# 21.net
KiCad netlist of a schematic drawn in Altium Designer
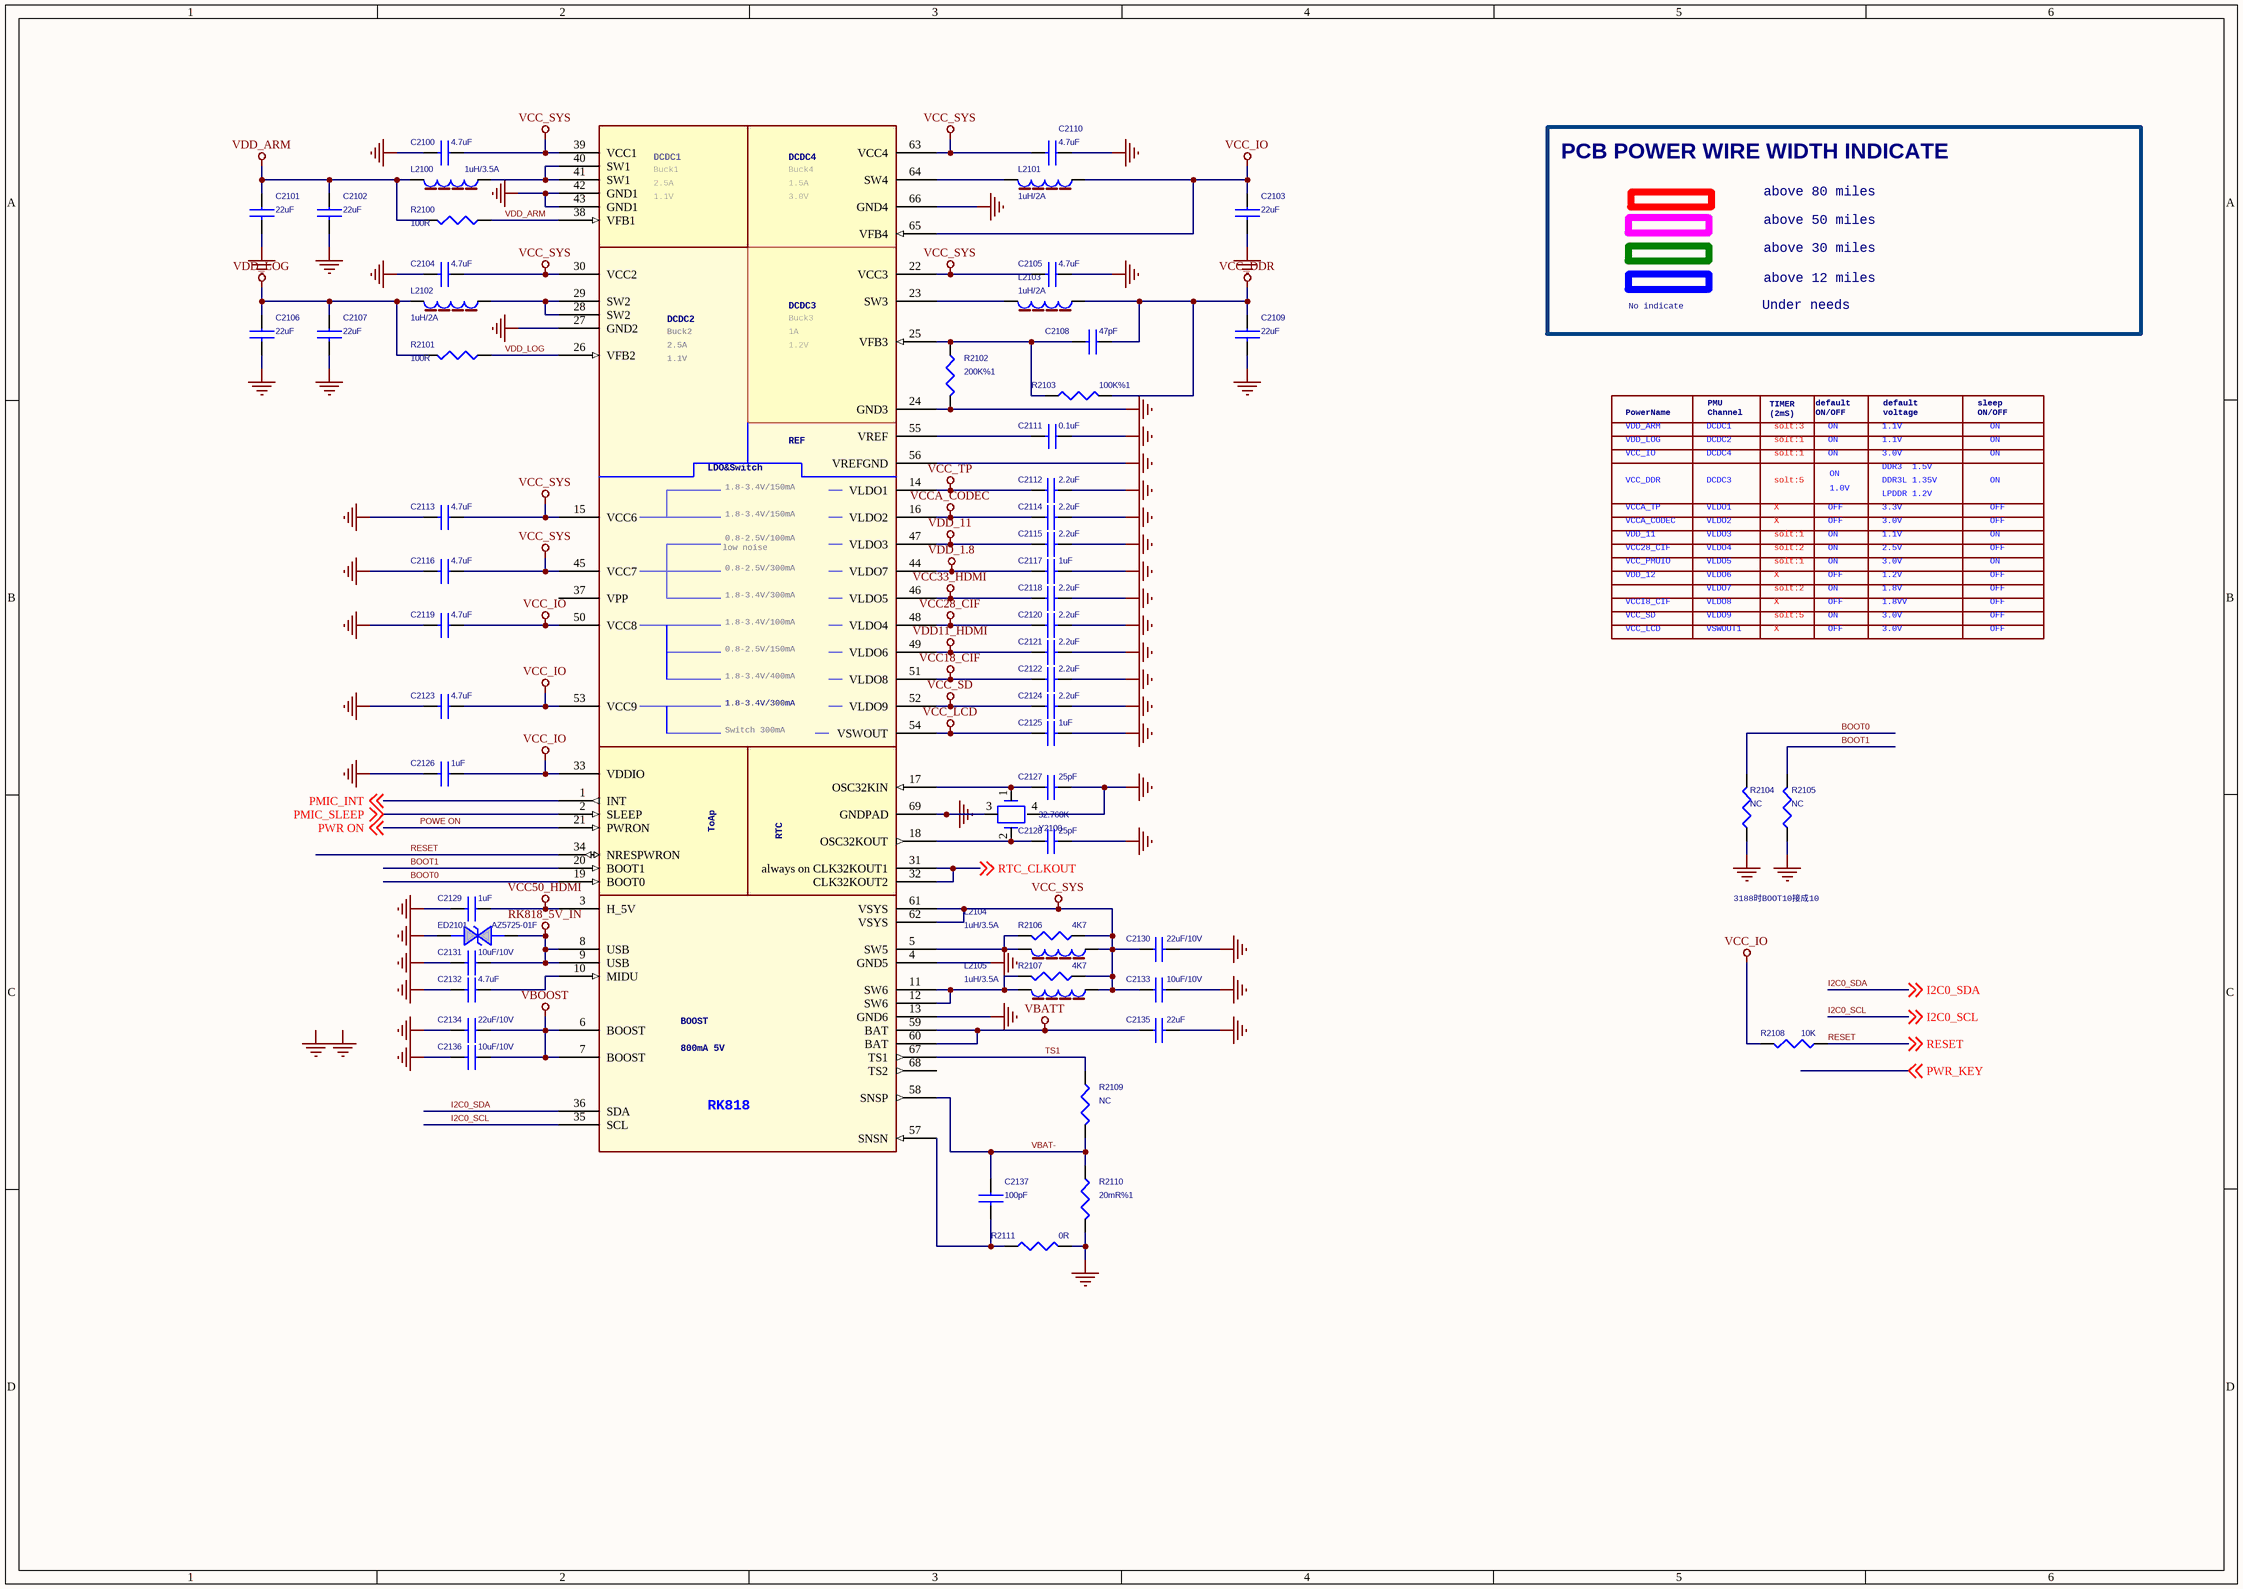
[diagram p0: 21.SchDoc]

(export (version "E")
  (design (tool "Eeschema 10.0.6"))
  (components
    (comp (ref "C2100") (value "4.7uF") (footprint "C0603") (libsource (lib "*") (part "CAP NP_4")))
    (comp (ref "C2101") (value "22uF") (footprint "C0805") (libsource (lib "*") (part "CAP NP_4")))
    (comp (ref "C2102") (value "22uF") (footprint "C0805") (libsource (lib "*") (part "CAP NP_4")))
    (comp (ref "C2103") (value "22uF") (footprint "C0805") (libsource (lib "*") (part "CAP NP_4")))
    (comp (ref "C2104") (value "4.7uF") (footprint "C0603") (libsource (lib "*") (part "CAP NP_4")))
    (comp (ref "C2105") (value "4.7uF") (footprint "C0603") (libsource (lib "*") (part "CAP NP_4")))
    (comp (ref "C2106") (value "22uF") (footprint "C0805") (libsource (lib "*") (part "CAP NP_4")))
    (comp (ref "C2107") (value "22uF") (footprint "C0805") (libsource (lib "*") (part "CAP NP_4")))
    (comp (ref "C2108") (value "47pF") (footprint "C0402") (libsource (lib "*") (part "CAP NP_4")))
    (comp (ref "C2109") (value "22uF") (footprint "C0805") (libsource (lib "*") (part "CAP NP_4")))
    (comp (ref "C2110") (value "4.7uF") (footprint "C0603") (libsource (lib "*") (part "CAP NP_4")))
    (comp (ref "C2111") (value "0.1uF") (footprint "C0402") (libsource (lib "*") (part "CAP NP_4")))
    (comp (ref "C2112") (value "2.2uF") (footprint "C0402") (libsource (lib "*") (part "CAP NP_4")))
    (comp (ref "C2113") (value "4.7uF") (footprint "C0603") (libsource (lib "*") (part "CAP NP_4")))
    (comp (ref "C2114") (value "2.2uF") (footprint "C0402") (libsource (lib "*") (part "CAP NP_4")))
    (comp (ref "C2115") (value "2.2uF") (footprint "C0402") (libsource (lib "*") (part "CAP NP_4")))
    (comp (ref "C2116") (value "4.7uF") (footprint "C0603") (libsource (lib "*") (part "CAP NP_4")))
    (comp (ref "C2117") (value "1uF") (footprint "C0402") (libsource (lib "*") (part "CAP NP_4")))
    (comp (ref "C2118") (value "2.2uF") (footprint "C0402") (libsource (lib "*") (part "CAP NP_4")))
    (comp (ref "C2119") (value "4.7uF") (footprint "C0603") (libsource (lib "*") (part "CAP NP_4")))
    (comp (ref "C2120") (value "2.2uF") (footprint "C0402") (libsource (lib "*") (part "CAP NP_4")))
    (comp (ref "C2121") (value "2.2uF") (footprint "C0402") (libsource (lib "*") (part "CAP NP_4")))
    (comp (ref "C2122") (value "2.2uF") (footprint "C0402") (libsource (lib "*") (part "CAP NP_4")))
    (comp (ref "C2123") (value "4.7uF") (footprint "C0603") (libsource (lib "*") (part "CAP NP_4")))
    (comp (ref "C2124") (value "2.2uF") (footprint "C0402") (libsource (lib "*") (part "CAP NP_4")))
    (comp (ref "C2125") (value "1uF") (footprint "C0402") (libsource (lib "*") (part "CAP NP_4")))
    (comp (ref "C2126") (value "1uF") (footprint "C0402") (libsource (lib "*") (part "CAP NP_4")))
    (comp (ref "C2127") (value "25pF") (footprint "C0402") (libsource (lib "*") (part "CAP NP_4")))
    (comp (ref "C2128") (value "25pF") (footprint "C0402") (libsource (lib "*") (part "CAP NP_4")))
    (comp (ref "C2129") (value "1uF") (footprint "C0402") (libsource (lib "*") (part "CAP NP_4")))
    (comp (ref "C2130") (value "22uF/10V") (footprint "C1206") (libsource (lib "*") (part "CAP NP_4")))
    (comp (ref "C2131") (value "10uF/10V") (footprint "C0805") (libsource (lib "*") (part "CAP NP_4")))
    (comp (ref "C2132") (value "4.7uF") (footprint "C0603") (libsource (lib "*") (part "CAP NP_4")))
    (comp (ref "C2133") (value "10uF/10V") (footprint "C0805") (libsource (lib "*") (part "CAP NP_4")))
    (comp (ref "C2134") (value "22uF/10V") (footprint "C1206") (libsource (lib "*") (part "CAP NP_4")))
    (comp (ref "C2135") (value "22uF") (footprint "C0805") (libsource (lib "*") (part "CAP NP_4")))
    (comp (ref "C2136") (value "10uF/10V") (footprint "C0805") (libsource (lib "*") (part "CAP NP_4")))
    (comp (ref "C2137") (value "100pF") (footprint "C0402") (libsource (lib "*") (part "CAP NP_4")))
    (comp (ref "ED2101")
      (value "AZ5725-01F")
      (footprint "E0402")
      (description "ESD")
      (libsource (lib "*") (part "DIODE BI-DIR TRIG"))
    )
    (comp (ref "L2100") (value "1uH/3.5A") (footprint "IND-4X4") (libsource (lib "*") (part "INDUCTOR_2")))
    (comp (ref "L2101") (value "1uH/2A") (footprint "IND-3X3") (libsource (lib "*") (part "INDUCTOR_2")))
    (comp (ref "L2102") (value "1uH/2A") (footprint "IND-3X3") (libsource (lib "*") (part "INDUCTOR_2")))
    (comp (ref "L2103") (value "1uH/2A") (footprint "IND-3X3") (libsource (lib "*") (part "INDUCTOR_2")))
    (comp (ref "L2104") (value "1uH/3.5A") (footprint "IND-4X4") (libsource (lib "*") (part "INDUCTOR_2")))
    (comp (ref "L2105") (value "1uH/3.5A") (footprint "IND-4X4") (libsource (lib "*") (part "INDUCTOR_2")))
    (comp (ref "R2100")
      (value "100R")
      (footprint "R0402")
      (description "RES,thick film,47KOhm,+/-5%,1/16W,SMD0402")
      (libsource (lib "*") (part "RESISTOR_1"))
    )
    (comp (ref "R2101")
      (value "100R")
      (footprint "R0402")
      (description "RES,thick film,47KOhm,+/-5%,1/16W,SMD0402")
      (libsource (lib "*") (part "RESISTOR_1"))
    )
    (comp (ref "R2102")
      (value "200K%1")
      (footprint "R0402")
      (description "RES,thick film,47KOhm,+/-5%,1/16W,SMD0402")
      (libsource (lib "*") (part "RESISTOR_1"))
    )
    (comp (ref "R2103")
      (value "100K%1")
      (footprint "R0402")
      (description "RES,thick film,47KOhm,+/-5%,1/16W,SMD0402")
      (libsource (lib "*") (part "RESISTOR_1"))
    )
    (comp (ref "R2104")
      (value "NC")
      (footprint "R0402")
      (description "RES,thick film,47KOhm,+/-5%,1/16W,SMD0402")
      (libsource (lib "*") (part "RESISTOR_1"))
    )
    (comp (ref "R2105")
      (value "NC")
      (footprint "R0402")
      (description "RES,thick film,47KOhm,+/-5%,1/16W,SMD0402")
      (libsource (lib "*") (part "RESISTOR_1"))
    )
    (comp (ref "R2106")
      (value "4K7")
      (footprint "R0402")
      (description "RES,thick film,47KOhm,+/-5%,1/16W,SMD0402")
      (libsource (lib "*") (part "RESISTOR_1"))
    )
    (comp (ref "R2107")
      (value "4K7")
      (footprint "R0402")
      (description "RES,thick film,47KOhm,+/-5%,1/16W,SMD0402")
      (libsource (lib "*") (part "RESISTOR_1"))
    )
    (comp (ref "R2108")
      (value "10K")
      (footprint "R0402")
      (description "RES,thick film,47KOhm,+/-5%,1/16W,SMD0402")
      (libsource (lib "*") (part "RESISTOR_1"))
    )
    (comp (ref "R2109")
      (value "NC")
      (footprint "R0402")
      (description "贴片电阻")
      (libsource (lib "*") (part "RESISTOR_1"))
    )
    (comp (ref "R2110")
      (value "20mR%1")
      (footprint "R1210")
      (description "贴片电阻")
      (libsource (lib "*") (part "RESISTOR_1"))
    )
    (comp (ref "R2111")
      (value "0R")
      (footprint "R0402")
      (description "贴片电阻")
      (libsource (lib "*") (part "RESISTOR_1"))
    )
    (comp (ref "U2100") (value "RK818") (footprint "QFN68") (libsource (lib "*") (part "RK818_1")))
    (comp (ref "Y2100")
      (value "32.768K")
      (footprint "CRY_MC146")
      (description "Crystal,32.768KHz,+/-30ppm,12pF,MC146,-10°C ~ +60   °C")
      (libsource (lib "*") (part "CRYSTAL_0"))
    )
  )
  (nets
    (net (code "1") (name "/BOOT0") (class "Default")
      (node (ref "R2104") (pin "1") (pinfunction "1_1") (pintype "passive"))
      (node (ref "U2100") (pin "19") (pinfunction "BOOT0_19") (pintype "input"))
    )
    (net (code "2") (name "/BOOT1") (class "Default")
      (node (ref "R2105") (pin "1") (pinfunction "1_1") (pintype "passive"))
      (node (ref "U2100") (pin "20") (pinfunction "BOOT1_20") (pintype "input"))
    )
    (net (code "3") (name "/TS1") (class "Default")
      (node (ref "R2109") (pin "1") (pinfunction "1_1") (pintype "passive"))
      (node (ref "U2100") (pin "67") (pinfunction "TS1_67") (pintype "output"))
    )
    (net (code "4") (name "/VBAT-") (class "Default")
      (node (ref "C2137") (pin "1") (pinfunction "1_1") (pintype "passive"))
      (node (ref "R2109") (pin "2") (pinfunction "2_2") (pintype "passive"))
      (node (ref "R2110") (pin "1") (pinfunction "1_1") (pintype "passive"))
      (node (ref "U2100") (pin "58") (pinfunction "SNSP_58") (pintype "output"))
    )
    (net (code "5") (name "GND") (class "Default")
      (node (ref "C2100") (pin "2") (pinfunction "2_2") (pintype "passive"))
      (node (ref "C2101") (pin "2") (pinfunction "2_2") (pintype "passive"))
      (node (ref "C2102") (pin "2") (pinfunction "2_2") (pintype "passive"))
      (node (ref "C2103") (pin "2") (pinfunction "2_2") (pintype "passive"))
      (node (ref "C2104") (pin "2") (pinfunction "2_2") (pintype "passive"))
      (node (ref "C2105") (pin "1") (pinfunction "1_1") (pintype "passive"))
      (node (ref "C2106") (pin "2") (pinfunction "2_2") (pintype "passive"))
      (node (ref "C2107") (pin "2") (pinfunction "2_2") (pintype "passive"))
      (node (ref "C2109") (pin "2") (pinfunction "2_2") (pintype "passive"))
      (node (ref "C2110") (pin "1") (pinfunction "1_1") (pintype "passive"))
      (node (ref "C2111") (pin "1") (pinfunction "1_1") (pintype "passive"))
      (node (ref "C2112") (pin "2") (pinfunction "2_2") (pintype "passive"))
      (node (ref "C2113") (pin "2") (pinfunction "2_2") (pintype "passive"))
      (node (ref "C2114") (pin "2") (pinfunction "2_2") (pintype "passive"))
      (node (ref "C2115") (pin "2") (pinfunction "2_2") (pintype "passive"))
      (node (ref "C2116") (pin "2") (pinfunction "2_2") (pintype "passive"))
      (node (ref "C2117") (pin "2") (pinfunction "2_2") (pintype "passive"))
      (node (ref "C2118") (pin "2") (pinfunction "2_2") (pintype "passive"))
      (node (ref "C2119") (pin "2") (pinfunction "2_2") (pintype "passive"))
      (node (ref "C2120") (pin "2") (pinfunction "2_2") (pintype "passive"))
      (node (ref "C2121") (pin "2") (pinfunction "2_2") (pintype "passive"))
      (node (ref "C2122") (pin "2") (pinfunction "2_2") (pintype "passive"))
      (node (ref "C2123") (pin "2") (pinfunction "2_2") (pintype "passive"))
      (node (ref "C2124") (pin "2") (pinfunction "2_2") (pintype "passive"))
      (node (ref "C2125") (pin "2") (pinfunction "2_2") (pintype "passive"))
      (node (ref "C2126") (pin "2") (pinfunction "2_2") (pintype "passive"))
      (node (ref "C2127") (pin "2") (pinfunction "2_2") (pintype "passive"))
      (node (ref "C2128") (pin "2") (pinfunction "2_2") (pintype "passive"))
      (node (ref "C2129") (pin "2") (pinfunction "2_2") (pintype "passive"))
      (node (ref "C2130") (pin "2") (pinfunction "2_2") (pintype "passive"))
      (node (ref "C2131") (pin "2") (pinfunction "2_2") (pintype "passive"))
      (node (ref "C2132") (pin "2") (pinfunction "2_2") (pintype "passive"))
      (node (ref "C2133") (pin "2") (pinfunction "2_2") (pintype "passive"))
      (node (ref "C2134") (pin "2") (pinfunction "2_2") (pintype "passive"))
      (node (ref "C2135") (pin "2") (pinfunction "2_2") (pintype "passive"))
      (node (ref "C2136") (pin "2") (pinfunction "2_2") (pintype "passive"))
      (node (ref "ED2101") (pin "1") (pinfunction "1_1") (pintype "passive"))
      (node (ref "R2102") (pin "1") (pinfunction "1_1") (pintype "passive"))
      (node (ref "R2104") (pin "2") (pinfunction "2_2") (pintype "passive"))
      (node (ref "R2105") (pin "2") (pinfunction "2_2") (pintype "passive"))
      (node (ref "R2110") (pin "2") (pinfunction "2_2") (pintype "passive"))
      (node (ref "R2111") (pin "2") (pinfunction "2_2") (pintype "passive"))
      (node (ref "U2100") (pin "13") (pinfunction "GND6_13") (pintype "power_in"))
      (node (ref "U2100") (pin "24") (pinfunction "GND3_24") (pintype "power_in"))
      (node (ref "U2100") (pin "27") (pinfunction "GND2_27") (pintype "power_in"))
      (node (ref "U2100") (pin "4") (pinfunction "GND5_4") (pintype "power_in"))
      (node (ref "U2100") (pin "42") (pinfunction "GND1_42") (pintype "power_in"))
      (node (ref "U2100") (pin "43") (pinfunction "GND1_43") (pintype "power_in"))
      (node (ref "U2100") (pin "56") (pinfunction "VREFGND_56") (pintype "power_in"))
      (node (ref "U2100") (pin "66") (pinfunction "GND4_66") (pintype "power_in"))
      (node (ref "U2100") (pin "69") (pinfunction "GNDPAD_69") (pintype "power_in"))
      (node (ref "Y2100") (pin "3") (pinfunction "3_3") (pintype "passive"))
      (node (ref "Y2100") (pin "4") (pinfunction "4_4") (pintype "passive"))
    )
    (net (code "6") (name "I2C0_SCL") (class "Default")
      (node (ref "U2100") (pin "35") (pinfunction "SCL_35") (pintype "open_collector"))
    )
    (net (code "7") (name "I2C0_SDA") (class "Default")
      (node (ref "U2100") (pin "36") (pinfunction "SDA_36") (pintype "open_collector"))
    )
    (net (code "8") (name "Net-(L2100-Pad2)") (class "Default")
      (node (ref "L2100") (pin "2") (pinfunction "2_2") (pintype "passive"))
      (node (ref "U2100") (pin "40") (pinfunction "SW1_40") (pintype "power_in"))
      (node (ref "U2100") (pin "41") (pinfunction "SW1_41") (pintype "power_in"))
    )
    (net (code "9") (name "Net-(L2102-Pad2)") (class "Default")
      (node (ref "L2102") (pin "2") (pinfunction "2_2") (pintype "passive"))
      (node (ref "U2100") (pin "28") (pinfunction "SW2_28") (pintype "power_in"))
      (node (ref "U2100") (pin "29") (pinfunction "SW2_29") (pintype "power_in"))
    )
    (net (code "10") (name "Net-(L2105-Pad1)") (class "Default")
      (node (ref "L2105") (pin "1") (pinfunction "1_1") (pintype "passive"))
      (node (ref "R2107") (pin "2") (pinfunction "2_2") (pintype "passive"))
      (node (ref "U2100") (pin "11") (pinfunction "SW6_11") (pintype "power_in"))
      (node (ref "U2100") (pin "12") (pinfunction "SW6_12") (pintype "power_in"))
    )
    (net (code "11") (name "Net-(U2100-MIDU)") (class "Default")
      (node (ref "C2132") (pin "1") (pinfunction "1_1") (pintype "passive"))
      (node (ref "U2100") (pin "10") (pinfunction "MIDU_10") (pintype "input"))
    )
    (net (code "12") (name "Net-(U2100-OSC32KIN)") (class "Default")
      (node (ref "C2127") (pin "1") (pinfunction "1_1") (pintype "passive"))
      (node (ref "U2100") (pin "17") (pinfunction "OSC32KIN_17") (pintype "input"))
      (node (ref "Y2100") (pin "1") (pinfunction "1_1") (pintype "passive"))
    )
    (net (code "13") (name "Net-(U2100-OSC32KOUT)") (class "Default")
      (node (ref "C2128") (pin "1") (pinfunction "1_1") (pintype "passive"))
      (node (ref "U2100") (pin "18") (pinfunction "OSC32KOUT_18") (pintype "output"))
      (node (ref "Y2100") (pin "2") (pinfunction "2_2") (pintype "passive"))
    )
    (net (code "14") (name "Net-(U2100-SNSN)") (class "Default")
      (node (ref "C2137") (pin "2") (pinfunction "2_2") (pintype "passive"))
      (node (ref "R2111") (pin "1") (pinfunction "1_1") (pintype "passive"))
      (node (ref "U2100") (pin "57") (pinfunction "SNSN_57") (pintype "input"))
    )
    (net (code "15") (name "Net-(U2100-SW3)") (class "Default")
      (node (ref "L2103") (pin "1") (pinfunction "1_1") (pintype "passive"))
      (node (ref "U2100") (pin "23") (pinfunction "SW3_23") (pintype "power_in"))
    )
    (net (code "16") (name "Net-(U2100-SW4)") (class "Default")
      (node (ref "L2101") (pin "1") (pinfunction "1_1") (pintype "passive"))
      (node (ref "U2100") (pin "64") (pinfunction "SW4_64") (pintype "power_in"))
    )
    (net (code "17") (name "Net-(U2100-SW5)") (class "Default")
      (node (ref "L2104") (pin "1") (pinfunction "1_1") (pintype "passive"))
      (node (ref "R2106") (pin "2") (pinfunction "2_2") (pintype "passive"))
      (node (ref "U2100") (pin "5") (pinfunction "SW5_5") (pintype "power_in"))
    )
    (net (code "18") (name "Net-(U2100-VFB3)") (class "Default")
      (node (ref "C2108") (pin "2") (pinfunction "2_2") (pintype "passive"))
      (node (ref "R2102") (pin "2") (pinfunction "2_2") (pintype "passive"))
      (node (ref "R2103") (pin "2") (pinfunction "2_2") (pintype "passive"))
      (node (ref "U2100") (pin "25") (pinfunction "VFB3_25") (pintype "input"))
    )
    (net (code "19") (name "Net-(U2100-VREF)") (class "Default")
      (node (ref "C2111") (pin "2") (pinfunction "2_2") (pintype "passive"))
      (node (ref "U2100") (pin "55") (pinfunction "VREF_55") (pintype "power_in"))
    )
    (net (code "20") (name "PMIC_INT") (class "Default")
      (node (ref "U2100") (pin "1") (pinfunction "INT_1") (pintype "output"))
    )
    (net (code "21") (name "PMIC_SLEEP") (class "Default")
      (node (ref "U2100") (pin "2") (pinfunction "SLEEP_2") (pintype "input"))
    )
    (net (code "22") (name "PWR ON") (class "Default")
      (node (ref "U2100") (pin "21") (pinfunction "PWRON_21") (pintype "input"))
    )
    (net (code "24") (name "RESET") (class "Default")
      (node (ref "R2108") (pin "2") (pinfunction "2_2") (pintype "passive"))
      (node (ref "U2100") (pin "34") (pinfunction "NRESPWRON_34") (pintype "bidirectional"))
    )
    (net (code "25") (name "RK818_5V_IN") (class "Default")
      (node (ref "C2131") (pin "1") (pinfunction "1_1") (pintype "passive"))
      (node (ref "ED2101") (pin "2") (pinfunction "2_2") (pintype "passive"))
      (node (ref "U2100") (pin "8") (pinfunction "USB_8") (pintype "power_in"))
      (node (ref "U2100") (pin "9") (pinfunction "USB_9") (pintype "power_in"))
    )
    (net (code "26") (name "RTC_CLKOUT") (class "Default")
      (node (ref "U2100") (pin "31") (pinfunction "always_on_CLK32KOUT1_31") (pintype "open_collector"))
      (node (ref "U2100") (pin "32") (pinfunction "CLK32KOUT2_32") (pintype "open_collector"))
    )
    (net (code "27") (name "VBATT") (class "Default")
      (node (ref "C2135") (pin "1") (pinfunction "1_1") (pintype "passive"))
      (node (ref "U2100") (pin "59") (pinfunction "BAT_59") (pintype "power_in"))
      (node (ref "U2100") (pin "60") (pinfunction "BAT_60") (pintype "power_in"))
    )
    (net (code "28") (name "VBOOST") (class "Default")
      (node (ref "C2134") (pin "1") (pinfunction "1_1") (pintype "passive"))
      (node (ref "C2136") (pin "1") (pinfunction "1_1") (pintype "passive"))
      (node (ref "U2100") (pin "6") (pinfunction "BOOST_6") (pintype "power_in"))
      (node (ref "U2100") (pin "7") (pinfunction "BOOST_7") (pintype "power_in"))
    )
    (net (code "29") (name "VCC18_CIF") (class "Default")
      (node (ref "C2122") (pin "1") (pinfunction "1_1") (pintype "passive"))
      (node (ref "U2100") (pin "51") (pinfunction "VLDO8_51") (pintype "power_in"))
    )
    (net (code "30") (name "VCC28_CIF") (class "Default")
      (node (ref "C2120") (pin "1") (pinfunction "1_1") (pintype "passive"))
      (node (ref "U2100") (pin "48") (pinfunction "VLDO4_48") (pintype "power_in"))
    )
    (net (code "31") (name "VCC33_HDMI") (class "Default")
      (node (ref "C2118") (pin "1") (pinfunction "1_1") (pintype "passive"))
      (node (ref "U2100") (pin "46") (pinfunction "VLDO5_46") (pintype "power_in"))
    )
    (net (code "32") (name "VCC50_HDMI") (class "Default")
      (node (ref "C2129") (pin "1") (pinfunction "1_1") (pintype "passive"))
      (node (ref "U2100") (pin "3") (pinfunction "H_5V_3") (pintype "power_in"))
    )
    (net (code "33") (name "VCCA_CODEC") (class "Default")
      (node (ref "C2114") (pin "1") (pinfunction "1_1") (pintype "passive"))
      (node (ref "U2100") (pin "16") (pinfunction "VLDO2_16") (pintype "power_in"))
    )
    (net (code "34") (name "VCC_DDR") (class "Default")
      (node (ref "C2108") (pin "1") (pinfunction "1_1") (pintype "passive"))
      (node (ref "C2109") (pin "1") (pinfunction "1_1") (pintype "passive"))
      (node (ref "L2103") (pin "2") (pinfunction "2_2") (pintype "passive"))
      (node (ref "R2103") (pin "1") (pinfunction "1_1") (pintype "passive"))
    )
    (net (code "35") (name "VCC_IO") (class "Default")
      (node (ref "C2103") (pin "1") (pinfunction "1_1") (pintype "passive"))
      (node (ref "C2119") (pin "1") (pinfunction "1_1") (pintype "passive"))
      (node (ref "C2123") (pin "1") (pinfunction "1_1") (pintype "passive"))
      (node (ref "C2126") (pin "1") (pinfunction "1_1") (pintype "passive"))
      (node (ref "L2101") (pin "2") (pinfunction "2_2") (pintype "passive"))
      (node (ref "R2108") (pin "1") (pinfunction "1_1") (pintype "passive"))
      (node (ref "U2100") (pin "33") (pinfunction "VDDIO_33") (pintype "power_in"))
      (node (ref "U2100") (pin "50") (pinfunction "VCC8_50") (pintype "power_in"))
      (node (ref "U2100") (pin "53") (pinfunction "VCC9_53") (pintype "power_in"))
      (node (ref "U2100") (pin "65") (pinfunction "VFB4_65") (pintype "input"))
    )
    (net (code "36") (name "VCC_LCD") (class "Default")
      (node (ref "C2125") (pin "1") (pinfunction "1_1") (pintype "passive"))
      (node (ref "U2100") (pin "54") (pinfunction "VSWOUT_54") (pintype "power_in"))
    )
    (net (code "37") (name "VCC_SD") (class "Default")
      (node (ref "C2124") (pin "1") (pinfunction "1_1") (pintype "passive"))
      (node (ref "U2100") (pin "52") (pinfunction "VLDO9_52") (pintype "power_in"))
    )
    (net (code "38") (name "VCC_SYS") (class "Default")
      (node (ref "C2100") (pin "1") (pinfunction "1_1") (pintype "passive"))
      (node (ref "C2104") (pin "1") (pinfunction "1_1") (pintype "passive"))
      (node (ref "C2105") (pin "2") (pinfunction "2_2") (pintype "passive"))
      (node (ref "C2110") (pin "2") (pinfunction "2_2") (pintype "passive"))
      (node (ref "C2113") (pin "1") (pinfunction "1_1") (pintype "passive"))
      (node (ref "C2116") (pin "1") (pinfunction "1_1") (pintype "passive"))
      (node (ref "C2130") (pin "1") (pinfunction "1_1") (pintype "passive"))
      (node (ref "C2133") (pin "1") (pinfunction "1_1") (pintype "passive"))
      (node (ref "L2104") (pin "2") (pinfunction "2_2") (pintype "passive"))
      (node (ref "L2105") (pin "2") (pinfunction "2_2") (pintype "passive"))
      (node (ref "R2106") (pin "1") (pinfunction "1_1") (pintype "passive"))
      (node (ref "R2107") (pin "1") (pinfunction "1_1") (pintype "passive"))
      (node (ref "U2100") (pin "15") (pinfunction "VCC6_15") (pintype "power_in"))
      (node (ref "U2100") (pin "22") (pinfunction "VCC3_22") (pintype "power_in"))
      (node (ref "U2100") (pin "30") (pinfunction "VCC2_30") (pintype "power_in"))
      (node (ref "U2100") (pin "39") (pinfunction "VCC1_39") (pintype "power_in"))
      (node (ref "U2100") (pin "45") (pinfunction "VCC7_45") (pintype "power_in"))
      (node (ref "U2100") (pin "61") (pinfunction "VSYS_61") (pintype "power_in"))
      (node (ref "U2100") (pin "62") (pinfunction "VSYS_62") (pintype "power_in"))
      (node (ref "U2100") (pin "63") (pinfunction "VCC4_63") (pintype "power_in"))
    )
    (net (code "39") (name "VCC_TP") (class "Default")
      (node (ref "C2112") (pin "1") (pinfunction "1_1") (pintype "passive"))
      (node (ref "U2100") (pin "14") (pinfunction "VLDO1_14") (pintype "power_in"))
    )
    (net (code "40") (name "VDD11_HDMI") (class "Default")
      (node (ref "C2121") (pin "1") (pinfunction "1_1") (pintype "passive"))
      (node (ref "U2100") (pin "49") (pinfunction "VLDO6_49") (pintype "power_in"))
    )
    (net (code "41") (name "VDD_1.8") (class "Default")
      (node (ref "C2117") (pin "1") (pinfunction "1_1") (pintype "passive"))
      (node (ref "U2100") (pin "44") (pinfunction "VLDO7_44") (pintype "power_in"))
    )
    (net (code "42") (name "VDD_11") (class "Default")
      (node (ref "C2115") (pin "1") (pinfunction "1_1") (pintype "passive"))
      (node (ref "U2100") (pin "47") (pinfunction "VLDO3_47") (pintype "power_in"))
    )
    (net (code "43") (name "VDD_ARM") (class "Default")
      (node (ref "C2101") (pin "1") (pinfunction "1_1") (pintype "passive"))
      (node (ref "C2102") (pin "1") (pinfunction "1_1") (pintype "passive"))
      (node (ref "L2100") (pin "1") (pinfunction "1_1") (pintype "passive"))
      (node (ref "R2100") (pin "1") (pinfunction "1_1") (pintype "passive"))
      (node (ref "R2100") (pin "2") (pinfunction "2_2") (pintype "passive"))
      (node (ref "U2100") (pin "38") (pinfunction "VFB1_38") (pintype "input"))
    )
    (net (code "44") (name "VDD_LOG") (class "Default")
      (node (ref "C2106") (pin "1") (pinfunction "1_1") (pintype "passive"))
      (node (ref "C2107") (pin "1") (pinfunction "1_1") (pintype "passive"))
      (node (ref "L2102") (pin "1") (pinfunction "1_1") (pintype "passive"))
      (node (ref "R2101") (pin "1") (pinfunction "1_1") (pintype "passive"))
      (node (ref "R2101") (pin "2") (pinfunction "2_2") (pintype "passive"))
      (node (ref "U2100") (pin "26") (pinfunction "VFB2_26") (pintype "input"))
    )
    (net (code "45") (name "unconnected-(U2100-TS2-Pad68)") (class "Default")
      (node (ref "U2100") (pin "68") (pinfunction "TS2_68") (pintype "output"))
    )
    (net (code "46") (name "unconnected-(U2100-VPP-Pad37)") (class "Default")
      (node (ref "U2100") (pin "37") (pinfunction "VPP_37") (pintype "passive"))
    )
  )
)
